# ONE_BOARD_INPUT.net
KiCad netlist of a schematic drawn in EAGLE
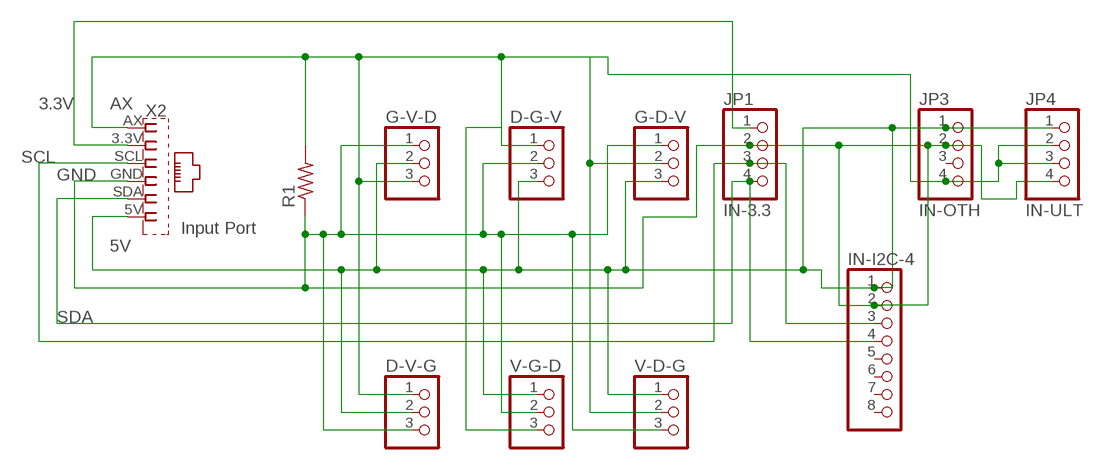
[diagram p0: schematic, sheet 1]

(export (version "E")
  (design (tool "Eeschema 10.0.6"))
  (components
    (comp (ref "D-G-V")
      (value "PINHD-1X3")
      (footprint "eagle-import:1X03")
      (libsource (lib "eagle-import") (part "PINHD-1X3"))
    )
    (comp (ref "D-V-G")
      (value "PINHD-1X3")
      (footprint "eagle-import:1X03")
      (libsource (lib "eagle-import") (part "PINHD-1X3"))
    )
    (comp (ref "G-D-V")
      (value "PINHD-1X3")
      (footprint "eagle-import:1X03")
      (libsource (lib "eagle-import") (part "PINHD-1X3"))
    )
    (comp (ref "G-V-D")
      (value "PINHD-1X3")
      (footprint "eagle-import:1X03")
      (libsource (lib "eagle-import") (part "PINHD-1X3"))
    )
    (comp (ref "IN-I2C-4")
      (value "PINHD-1X8")
      (footprint "eagle-import:1X08")
      (libsource (lib "eagle-import") (part "PINHD-1X8"))
    )
    (comp (ref "JP1")
      (value "IN-3.3")
      (footprint "eagle-import:1X04")
      (libsource (lib "eagle-import") (part "PINHD-1X4"))
    )
    (comp (ref "JP3")
      (value "IN-OTH")
      (footprint "eagle-import:1X04")
      (libsource (lib "eagle-import") (part "PINHD-1X4"))
    )
    (comp (ref "JP4")
      (value "IN-ULT")
      (footprint "eagle-import:1X04")
      (libsource (lib "eagle-import") (part "PINHD-1X4"))
    )
    (comp (ref "R1")
      (value "R-US_0207/10")
      (footprint "eagle-import:0207_10")
      (libsource (lib "eagle-import") (part "R-US_0207/10"))
    )
    (comp (ref "V-D-G")
      (value "PINHD-1X3")
      (footprint "eagle-import:1X03")
      (libsource (lib "eagle-import") (part "PINHD-1X3"))
    )
    (comp (ref "V-G-D")
      (value "PINHD-1X3")
      (footprint "eagle-import:1X03")
      (libsource (lib "eagle-import") (part "PINHD-1X3"))
    )
    (comp (ref "X2")
      (value "Input Port")
      (footprint "eagle-import:ELEMENTORY-IN-SEN")
      (libsource (lib "eagle-import") (part "ELEMENTORY-RJ11INPUT-DEVICE"))
    )
  )
  (nets
    (net (code "1") (name "/3.3V") (class "Default")
      (node (ref "JP1") (pin "1") (pinfunction "1_1") (pintype "passive"))
      (node (ref "X2") (pin "3.3V") (pinfunction "2_3.3V") (pintype "passive"))
    )
    (net (code "2") (name "/5V") (class "Default")
      (node (ref "D-G-V") (pin "3") (pinfunction "3_3") (pintype "passive"))
      (node (ref "D-V-G") (pin "2") (pinfunction "2_2") (pintype "passive"))
      (node (ref "G-D-V") (pin "3") (pinfunction "3_3") (pintype "passive"))
      (node (ref "G-V-D") (pin "2") (pinfunction "2_2") (pintype "passive"))
      (node (ref "IN-I2C-4") (pin "1") (pinfunction "1_1") (pintype "passive"))
      (node (ref "JP3") (pin "1") (pinfunction "1_1") (pintype "passive"))
      (node (ref "JP4") (pin "1") (pinfunction "1_1") (pintype "passive"))
      (node (ref "V-D-G") (pin "1") (pinfunction "1_1") (pintype "passive"))
      (node (ref "V-G-D") (pin "1") (pinfunction "1_1") (pintype "passive"))
      (node (ref "X2") (pin "5V") (pinfunction "6_5V") (pintype "passive"))
    )
    (net (code "3") (name "/AX") (class "Default")
      (node (ref "D-G-V") (pin "1") (pinfunction "1_1") (pintype "passive"))
      (node (ref "D-V-G") (pin "1") (pinfunction "1_1") (pintype "passive"))
      (node (ref "G-D-V") (pin "2") (pinfunction "2_2") (pintype "passive"))
      (node (ref "G-V-D") (pin "3") (pinfunction "3_3") (pintype "passive"))
      (node (ref "JP3") (pin "4") (pinfunction "4_4") (pintype "passive"))
      (node (ref "JP4") (pin "2") (pinfunction "2_2") (pintype "passive"))
      (node (ref "JP4") (pin "3") (pinfunction "3_3") (pintype "passive"))
      (node (ref "R1") (pin "2") (pinfunction "2_2") (pintype "passive"))
      (node (ref "V-D-G") (pin "2") (pinfunction "2_2") (pintype "passive"))
      (node (ref "V-G-D") (pin "3") (pinfunction "3_3") (pintype "passive"))
      (node (ref "X2") (pin "AX") (pinfunction "1_AX") (pintype "passive"))
    )
    (net (code "4") (name "/GND") (class "Default")
      (node (ref "D-G-V") (pin "2") (pinfunction "2_2") (pintype "passive"))
      (node (ref "D-V-G") (pin "3") (pinfunction "3_3") (pintype "passive"))
      (node (ref "G-D-V") (pin "1") (pinfunction "1_1") (pintype "passive"))
      (node (ref "G-V-D") (pin "1") (pinfunction "1_1") (pintype "passive"))
      (node (ref "IN-I2C-4") (pin "2") (pinfunction "2_2") (pintype "passive"))
      (node (ref "JP1") (pin "2") (pinfunction "2_2") (pintype "passive"))
      (node (ref "JP3") (pin "2") (pinfunction "2_2") (pintype "passive"))
      (node (ref "JP4") (pin "4") (pinfunction "4_4") (pintype "passive"))
      (node (ref "R1") (pin "1") (pinfunction "1_1") (pintype "passive"))
      (node (ref "V-D-G") (pin "3") (pinfunction "3_3") (pintype "passive"))
      (node (ref "V-G-D") (pin "2") (pinfunction "2_2") (pintype "passive"))
      (node (ref "X2") (pin "GND") (pinfunction "4_GND") (pintype "passive"))
    )
    (net (code "5") (name "/SCL") (class "Default")
      (node (ref "IN-I2C-4") (pin "3") (pinfunction "3_3") (pintype "passive"))
      (node (ref "JP1") (pin "3") (pinfunction "3_3") (pintype "passive"))
      (node (ref "X2") (pin "SCL") (pinfunction "3_SCL") (pintype "passive"))
    )
    (net (code "6") (name "/SDA") (class "Default")
      (node (ref "IN-I2C-4") (pin "4") (pinfunction "4_4") (pintype "passive"))
      (node (ref "JP1") (pin "4") (pinfunction "4_4") (pintype "passive"))
      (node (ref "X2") (pin "SDA") (pinfunction "5_SDA") (pintype "passive"))
    )
    (net (code "7") (name "unconnected-(IN-I2C-4-Pad5)") (class "Default")
      (node (ref "IN-I2C-4") (pin "5") (pinfunction "5_5") (pintype "passive"))
    )
    (net (code "8") (name "unconnected-(IN-I2C-4-Pad6)") (class "Default")
      (node (ref "IN-I2C-4") (pin "6") (pinfunction "6_6") (pintype "passive"))
    )
    (net (code "9") (name "unconnected-(IN-I2C-4-Pad7)") (class "Default")
      (node (ref "IN-I2C-4") (pin "7") (pinfunction "7_7") (pintype "passive"))
    )
    (net (code "10") (name "unconnected-(IN-I2C-4-Pad8)") (class "Default")
      (node (ref "IN-I2C-4") (pin "8") (pinfunction "8_8") (pintype "passive"))
    )
    (net (code "11") (name "unconnected-(JP3-Pad3)") (class "Default")
      (node (ref "JP3") (pin "3") (pinfunction "3_3") (pintype "passive"))
    )
  )
)
